# programmer.net
KiCad netlist of a schematic drawn in EAGLE
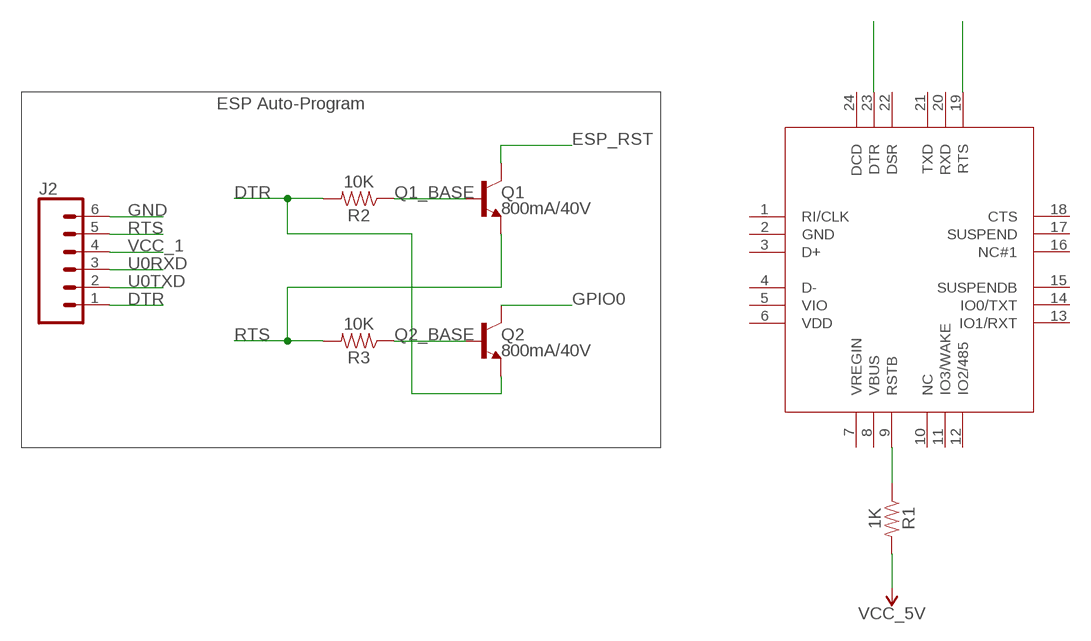
[diagram p0: schematic, sheet 1]

(export (version "E")
  (design (tool "Eeschema 10.0.6"))
  (components
    (comp (ref "J2")
      (value "CONN_06SILK_FEMALE_PTH")
      (footprint "eagle-import:1X06")
      (libsource (lib "eagle-import") (part "CONN_06SILK_FEMALE_PTH"))
    )
    (comp (ref "Q1")
      (value "800mA/40V")
      (footprint "eagle-import:SOT23-3")
      (libsource (lib "eagle-import") (part "TRANS_NPN-MMBT2222AL"))
    )
    (comp (ref "Q2")
      (value "800mA/40V")
      (footprint "eagle-import:SOT23-3")
      (libsource (lib "eagle-import") (part "TRANS_NPN-MMBT2222AL"))
    )
    (comp (ref "R1")
      (value "1K")
      (footprint "eagle-import:0805")
      (libsource (lib "eagle-import") (part "RESISTOR"))
    )
    (comp (ref "R2")
      (value "10K")
      (footprint "eagle-import:0805")
      (libsource (lib "eagle-import") (part "RESISTOR"))
    )
    (comp (ref "R3")
      (value "10K")
      (footprint "eagle-import:0805")
      (libsource (lib "eagle-import") (part "RESISTOR"))
    )
    (comp (ref "U$1")
      (value "CP2102")
      (footprint "eagle-import:CP2102_QFN24")
      (libsource (lib "eagle-import") (part "CP2102"))
    )
  )
  (nets
    (net (code "1") (name "/DTR") (class "Default")
      (node (ref "J2") (pin "1") (pinfunction "1_1") (pintype "passive"))
      (node (ref "Q2") (pin "2") (pinfunction "E_2") (pintype "passive"))
      (node (ref "R2") (pin "2") (pinfunction "2_2") (pintype "passive"))
    )
    (net (code "2") (name "/ESP_RST") (class "Default")
      (node (ref "Q1") (pin "3") (pinfunction "C_3") (pintype "passive"))
    )
    (net (code "3") (name "/GND") (class "Default")
      (node (ref "J2") (pin "6") (pinfunction "6_6") (pintype "passive"))
    )
    (net (code "4") (name "/GPIO0") (class "Default")
      (node (ref "Q2") (pin "3") (pinfunction "C_3") (pintype "passive"))
    )
    (net (code "5") (name "/Q1_BASE") (class "Default")
      (node (ref "Q1") (pin "1") (pinfunction "B_1") (pintype "passive"))
      (node (ref "R2") (pin "1") (pinfunction "1_1") (pintype "passive"))
    )
    (net (code "6") (name "/Q2_BASE") (class "Default")
      (node (ref "Q2") (pin "1") (pinfunction "B_1") (pintype "passive"))
      (node (ref "R3") (pin "1") (pinfunction "1_1") (pintype "passive"))
    )
    (net (code "7") (name "/RTS") (class "Default")
      (node (ref "J2") (pin "5") (pinfunction "5_5") (pintype "passive"))
      (node (ref "Q1") (pin "2") (pinfunction "E_2") (pintype "passive"))
      (node (ref "R3") (pin "2") (pinfunction "2_2") (pintype "passive"))
    )
    (net (code "8") (name "/U0RXD") (class "Default")
      (node (ref "J2") (pin "3") (pinfunction "3_3") (pintype "passive"))
    )
    (net (code "9") (name "/U0TXD") (class "Default")
      (node (ref "J2") (pin "2") (pinfunction "2_2") (pintype "passive"))
    )
    (net (code "10") (name "Net-(U$1-RSTB)") (class "Default")
      (node (ref "R1") (pin "1") (pinfunction "1_1") (pintype "passive"))
      (node (ref "U$1") (pin "9") (pinfunction "RSTB_9") (pintype "bidirectional"))
    )
    (net (code "11") (name "VCC_5V") (class "Default")
      (node (ref "J2") (pin "4") (pinfunction "4_4") (pintype "passive"))
      (node (ref "R1") (pin "2") (pinfunction "2_2") (pintype "passive"))
    )
    (net (code "12") (name "unconnected-(U$1-CTS-Pad18)") (class "Default")
      (node (ref "U$1") (pin "18") (pinfunction "CTS_18") (pintype "bidirectional"))
    )
    (net (code "13") (name "unconnected-(U$1-D+-Pad3)") (class "Default")
      (node (ref "U$1") (pin "3") (pinfunction "D+_3") (pintype "bidirectional"))
    )
    (net (code "14") (name "unconnected-(U$1-D--Pad4)") (class "Default")
      (node (ref "U$1") (pin "4") (pinfunction "D-_4") (pintype "bidirectional"))
    )
    (net (code "15") (name "unconnected-(U$1-DCD-Pad24)") (class "Default")
      (node (ref "U$1") (pin "24") (pinfunction "DCD_24") (pintype "bidirectional"))
    )
    (net (code "16") (name "unconnected-(U$1-DSR-Pad22)") (class "Default")
      (node (ref "U$1") (pin "22") (pinfunction "DSR_22") (pintype "bidirectional"))
    )
    (net (code "17") (name "unconnected-(U$1-DTR-Pad23)") (class "Default")
      (node (ref "U$1") (pin "23") (pinfunction "DTR_23") (pintype "bidirectional"))
    )
    (net (code "18") (name "unconnected-(U$1-GND-Pad2)") (class "Default")
      (node (ref "U$1") (pin "2") (pinfunction "GND_2") (pintype "bidirectional"))
    )
    (net (code "19") (name "unconnected-(U$1-IO0{slash}TXT-Pad14)") (class "Default")
      (node (ref "U$1") (pin "14") (pinfunction "IO0/TXT_14") (pintype "bidirectional"))
    )
    (net (code "20") (name "unconnected-(U$1-IO1{slash}RXT-Pad13)") (class "Default")
      (node (ref "U$1") (pin "13") (pinfunction "IO1/RXT_13") (pintype "bidirectional"))
    )
    (net (code "21") (name "unconnected-(U$1-IO2{slash}485-Pad12)") (class "Default")
      (node (ref "U$1") (pin "12") (pinfunction "IO2/485_12") (pintype "bidirectional"))
    )
    (net (code "22") (name "unconnected-(U$1-IO3{slash}WAKE-Pad11)") (class "Default")
      (node (ref "U$1") (pin "11") (pinfunction "IO3/WAKE_11") (pintype "bidirectional"))
    )
    (net (code "23") (name "unconnected-(U$1-NC#1-Pad16)") (class "Default")
      (node (ref "U$1") (pin "16") (pinfunction "NC#1_16") (pintype "bidirectional"))
    )
    (net (code "24") (name "unconnected-(U$1-NC-Pad10)") (class "Default")
      (node (ref "U$1") (pin "10") (pinfunction "NC_10") (pintype "bidirectional"))
    )
    (net (code "25") (name "unconnected-(U$1-RI{slash}CLK-Pad1)") (class "Default")
      (node (ref "U$1") (pin "1") (pinfunction "RI/CLK_1") (pintype "bidirectional"))
    )
    (net (code "26") (name "unconnected-(U$1-RTS-Pad19)") (class "Default")
      (node (ref "U$1") (pin "19") (pinfunction "RTS_19") (pintype "bidirectional"))
    )
    (net (code "27") (name "unconnected-(U$1-RXD-Pad20)") (class "Default")
      (node (ref "U$1") (pin "20") (pinfunction "RXD_20") (pintype "bidirectional"))
    )
    (net (code "28") (name "unconnected-(U$1-SUSPEND-Pad17)") (class "Default")
      (node (ref "U$1") (pin "17") (pinfunction "SUSPEND_17") (pintype "bidirectional"))
    )
    (net (code "29") (name "unconnected-(U$1-SUSPENDB-Pad15)") (class "Default")
      (node (ref "U$1") (pin "15") (pinfunction "SUSPENDB_15") (pintype "bidirectional"))
    )
    (net (code "30") (name "unconnected-(U$1-TXD-Pad21)") (class "Default")
      (node (ref "U$1") (pin "21") (pinfunction "TXD_21") (pintype "bidirectional"))
    )
    (net (code "31") (name "unconnected-(U$1-VBUS-Pad8)") (class "Default")
      (node (ref "U$1") (pin "8") (pinfunction "VBUS_8") (pintype "bidirectional"))
    )
    (net (code "32") (name "unconnected-(U$1-VDD-Pad6)") (class "Default")
      (node (ref "U$1") (pin "6") (pinfunction "VDD_6") (pintype "bidirectional"))
    )
    (net (code "33") (name "unconnected-(U$1-VIO-Pad5)") (class "Default")
      (node (ref "U$1") (pin "5") (pinfunction "VIO_5") (pintype "bidirectional"))
    )
    (net (code "34") (name "unconnected-(U$1-VREGIN-Pad7)") (class "Default")
      (node (ref "U$1") (pin "7") (pinfunction "VREGIN_7") (pintype "bidirectional"))
    )
  )
)
